# if-455-to-12khz.net
KiCad netlist of a schematic drawn in EAGLE
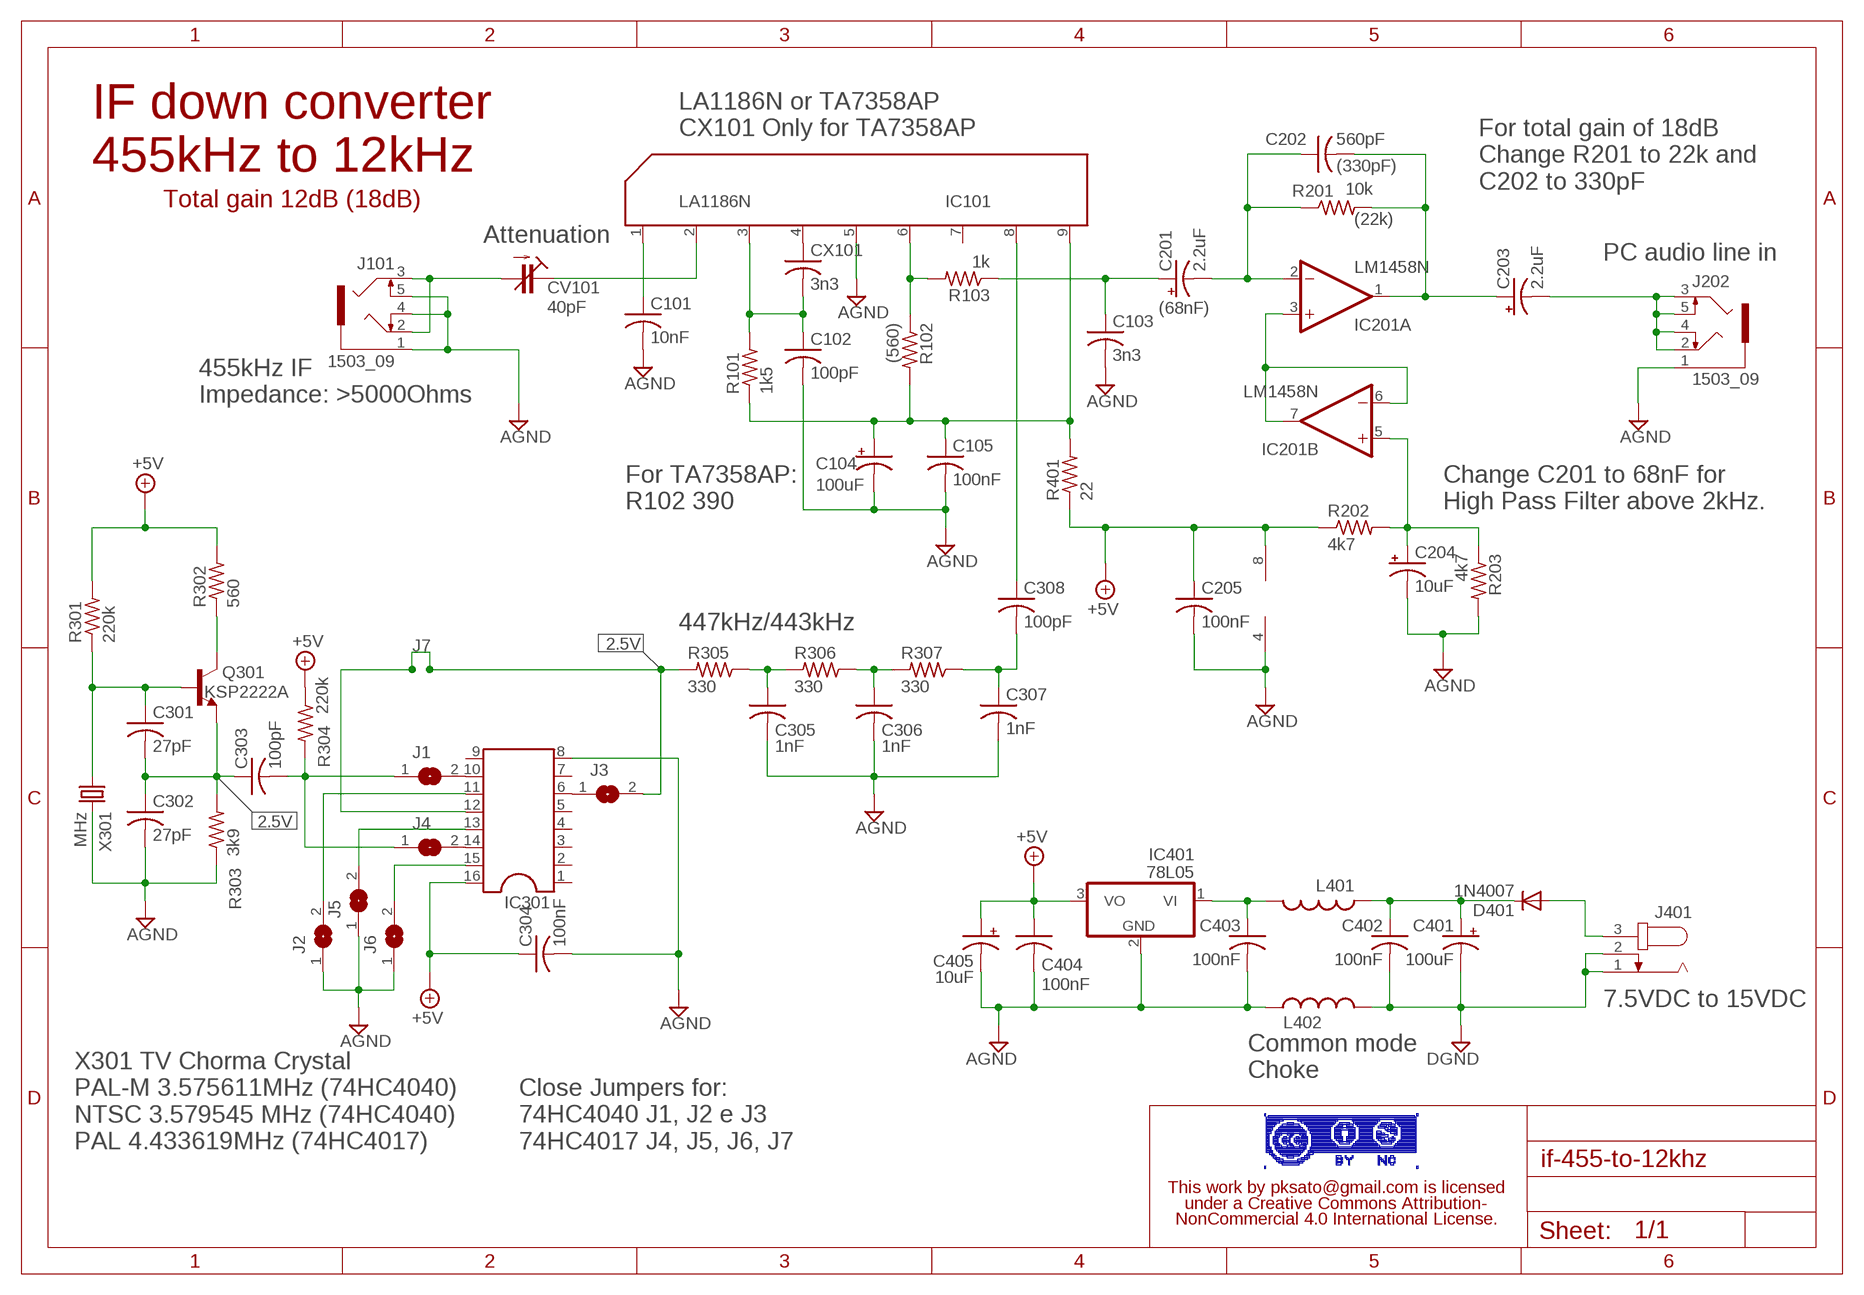
[diagram p0: schematic, sheet 1]

(export (version "E")
  (design (tool "Eeschema 10.0.6"))
  (components
    (comp (ref "C101")
      (value "10nF")
      (footprint "eagle-import:C050-025X075")
      (libsource (lib "eagle-import") (part "C-US050-025X075"))
    )
    (comp (ref "C102")
      (value "100pF")
      (footprint "eagle-import:C050-025X075")
      (libsource (lib "eagle-import") (part "C-US050-025X075"))
    )
    (comp (ref "C103")
      (value "3n3")
      (footprint "eagle-import:C050-025X075")
      (libsource (lib "eagle-import") (part "C-US050-025X075"))
    )
    (comp (ref "C104")
      (value "100uF")
      (footprint "eagle-import:E2,5-5")
      (libsource (lib "eagle-import") (part "CPOL-USE2.5-5"))
    )
    (comp (ref "C105")
      (value "100nF")
      (footprint "eagle-import:C050-025X075")
      (libsource (lib "eagle-import") (part "C-US050-025X075"))
    )
    (comp (ref "C201")
      (value "2.2uF")
      (footprint "eagle-import:E5-5")
      (libsource (lib "eagle-import") (part "CPOL-USE5-5"))
    )
    (comp (ref "C202")
      (value "560pF")
      (footprint "eagle-import:C050-025X075")
      (libsource (lib "eagle-import") (part "C-US050-025X075"))
    )
    (comp (ref "C203")
      (value "2.2uF")
      (footprint "eagle-import:E2,5-5")
      (libsource (lib "eagle-import") (part "CPOL-USE2.5-5"))
    )
    (comp (ref "C204")
      (value "10uF")
      (footprint "eagle-import:E2,5-5")
      (libsource (lib "eagle-import") (part "CPOL-USE2.5-5"))
    )
    (comp (ref "C205")
      (value "100nF")
      (footprint "eagle-import:C050-025X075")
      (libsource (lib "eagle-import") (part "C-US050-025X075"))
    )
    (comp (ref "C301")
      (value "27pF")
      (footprint "eagle-import:C050-025X075")
      (libsource (lib "eagle-import") (part "C-US050-025X075"))
    )
    (comp (ref "C302")
      (value "27pF")
      (footprint "eagle-import:C050-025X075")
      (libsource (lib "eagle-import") (part "C-US050-025X075"))
    )
    (comp (ref "C303")
      (value "100pF")
      (footprint "eagle-import:C050-025X075")
      (libsource (lib "eagle-import") (part "C-US050-025X075"))
    )
    (comp (ref "C304")
      (value "100nF")
      (footprint "eagle-import:C050-025X075")
      (libsource (lib "eagle-import") (part "C-US050-025X075"))
    )
    (comp (ref "C305")
      (value "1nF")
      (footprint "eagle-import:C050-025X075")
      (libsource (lib "eagle-import") (part "C-US050-025X075"))
    )
    (comp (ref "C306")
      (value "1nF")
      (footprint "eagle-import:C050-025X075")
      (libsource (lib "eagle-import") (part "C-US050-025X075"))
    )
    (comp (ref "C307")
      (value "1nF")
      (footprint "eagle-import:C050-025X075")
      (libsource (lib "eagle-import") (part "C-US050-025X075"))
    )
    (comp (ref "C308")
      (value "100pF")
      (footprint "eagle-import:C050-025X075")
      (libsource (lib "eagle-import") (part "C-US050-025X075"))
    )
    (comp (ref "C401")
      (value "100uF")
      (footprint "eagle-import:E2,5-5")
      (libsource (lib "eagle-import") (part "CPOL-USE2.5-5"))
    )
    (comp (ref "C402")
      (value "100nF")
      (footprint "eagle-import:C050-025X075")
      (libsource (lib "eagle-import") (part "C-US050-025X075"))
    )
    (comp (ref "C403")
      (value "100nF")
      (footprint "eagle-import:C050-025X075")
      (libsource (lib "eagle-import") (part "C-US050-025X075"))
    )
    (comp (ref "C404")
      (value "100nF")
      (footprint "eagle-import:C050-025X075")
      (libsource (lib "eagle-import") (part "C-US050-025X075"))
    )
    (comp (ref "C405")
      (value "10uF")
      (footprint "eagle-import:E2,5-5")
      (libsource (lib "eagle-import") (part "CPOL-USE2.5-5"))
    )
    (comp (ref "CV101")
      (value "40pF")
      (footprint "eagle-import:CTRIMTZ03")
      (libsource (lib "eagle-import") (part "C-TRIMMTZ03"))
    )
    (comp (ref "CX101")
      (value "3n3")
      (footprint "eagle-import:C025-025X050")
      (libsource (lib "eagle-import") (part "C-US025-025X050"))
    )
    (comp (ref "D401")
      (value "1N4007")
      (footprint "eagle-import:DO41-10")
      (libsource (lib "eagle-import") (part "1N4004"))
    )
    (comp (ref "IC101")
      (value "LA1186N")
      (footprint "eagle-import:SIP09")
      (libsource (lib "eagle-import") (part "SIP09"))
    )
    (comp (ref "IC201")
      (value "LM1458N")
      (footprint "eagle-import:DIL08")
      (libsource (lib "eagle-import") (part "1458NLM"))
    )
    (comp (ref "IC301")
      (value "DIL16")
      (footprint "eagle-import:DIL16")
      (libsource (lib "eagle-import") (part "DIL16"))
    )
    (comp (ref "IC401")
      (value "78L05")
      (footprint "eagle-import:TO92-")
      (libsource (lib "eagle-import") (part "78L-L05"))
    )
    (comp (ref "J1") (value "SJ") (footprint "eagle-import:SJ") (libsource (lib "eagle-import") (part "SJ")))
    (comp (ref "J2") (value "SJ") (footprint "eagle-import:SJ") (libsource (lib "eagle-import") (part "SJ")))
    (comp (ref "J3") (value "SJ") (footprint "eagle-import:SJ") (libsource (lib "eagle-import") (part "SJ")))
    (comp (ref "J4") (value "SJ") (footprint "eagle-import:SJ") (libsource (lib "eagle-import") (part "SJ")))
    (comp (ref "J5") (value "SJ") (footprint "eagle-import:SJ") (libsource (lib "eagle-import") (part "SJ")))
    (comp (ref "J6") (value "SJ") (footprint "eagle-import:SJ") (libsource (lib "eagle-import") (part "SJ")))
    (comp (ref "J101")
      (value "1503_09")
      (footprint "eagle-import:1503_09")
      (libsource (lib "eagle-import") (part "1503_09"))
    )
    (comp (ref "J202")
      (value "1503_09")
      (footprint "eagle-import:1503_09")
      (libsource (lib "eagle-import") (part "1503_09"))
    )
    (comp (ref "J401")
      (value "JACK-PLUG0")
      (footprint "eagle-import:SPC4077")
      (libsource (lib "eagle-import") (part "JACK-PLUG0"))
    )
    (comp (ref "L401")
      (value "L-US0207/10")
      (footprint "eagle-import:0207_10")
      (libsource (lib "eagle-import") (part "L-US0207/10"))
    )
    (comp (ref "L402")
      (value "L-US0207/10")
      (footprint "eagle-import:0207_10")
      (libsource (lib "eagle-import") (part "L-US0207/10"))
    )
    (comp (ref "Q301")
      (value "KSP2222A")
      (footprint "eagle-import:TO92-EBC")
      (libsource (lib "eagle-import") (part "-NPN-TO92-EBC2N2222"))
    )
    (comp (ref "R101")
      (value "1k5")
      (footprint "eagle-import:0207_10")
      (libsource (lib "eagle-import") (part "R-US_0207/10"))
    )
    (comp (ref "R102")
      (value "(560)")
      (footprint "eagle-import:0207_10")
      (libsource (lib "eagle-import") (part "R-US_0207/10"))
    )
    (comp (ref "R103")
      (value "1k")
      (footprint "eagle-import:0207_10")
      (libsource (lib "eagle-import") (part "R-US_0207/10"))
    )
    (comp (ref "R201")
      (value "10k")
      (footprint "eagle-import:0207_10")
      (libsource (lib "eagle-import") (part "R-US_0207/10"))
    )
    (comp (ref "R202")
      (value "4k7")
      (footprint "eagle-import:0207_10")
      (libsource (lib "eagle-import") (part "R-US_0207/10"))
    )
    (comp (ref "R203")
      (value "4k7")
      (footprint "eagle-import:0207_10")
      (libsource (lib "eagle-import") (part "R-US_0207/10"))
    )
    (comp (ref "R301")
      (value "220k")
      (footprint "eagle-import:0207_10")
      (libsource (lib "eagle-import") (part "R-US_0207/10"))
    )
    (comp (ref "R302")
      (value "560")
      (footprint "eagle-import:0207_10")
      (libsource (lib "eagle-import") (part "R-US_0207/10"))
    )
    (comp (ref "R303")
      (value "3k9")
      (footprint "eagle-import:0207_10")
      (libsource (lib "eagle-import") (part "R-US_0207/10"))
    )
    (comp (ref "R304")
      (value "220k")
      (footprint "eagle-import:0207_10")
      (libsource (lib "eagle-import") (part "R-US_0207/10"))
    )
    (comp (ref "R305")
      (value "330")
      (footprint "eagle-import:0207_10")
      (libsource (lib "eagle-import") (part "R-US_0207/10"))
    )
    (comp (ref "R306")
      (value "330")
      (footprint "eagle-import:0207_10")
      (libsource (lib "eagle-import") (part "R-US_0207/10"))
    )
    (comp (ref "R307")
      (value "330")
      (footprint "eagle-import:0207_10")
      (libsource (lib "eagle-import") (part "R-US_0207/10"))
    )
    (comp (ref "R401")
      (value "22")
      (footprint "eagle-import:0207_10")
      (libsource (lib "eagle-import") (part "R-US_0207/10"))
    )
    (comp (ref "X301")
      (value "MHz")
      (footprint "eagle-import:HC49U-LM")
      (libsource (lib "eagle-import") (part "CRYSTALHC49U-LM"))
    )
  )
  (nets
    (net (code "1") (name "+5V") (class "Default")
      (node (ref "C205") (pin "1") (pinfunction "1_1") (pintype "passive"))
      (node (ref "C304") (pin "1") (pinfunction "1_1") (pintype "passive"))
      (node (ref "C404") (pin "1") (pinfunction "1_1") (pintype "passive"))
      (node (ref "C405") (pin "+") (pinfunction "+_+") (pintype "passive"))
      (node (ref "IC201") (pin "8") (pinfunction "V+_8") (pintype "power_in"))
      (node (ref "IC301") (pin "16") (pinfunction "16_16") (pintype "passive"))
      (node (ref "IC401") (pin "3") (pinfunction "VO_3") (pintype "passive"))
      (node (ref "R202") (pin "1") (pinfunction "1_1") (pintype "passive"))
      (node (ref "R301") (pin "2") (pinfunction "2_2") (pintype "passive"))
      (node (ref "R302") (pin "2") (pinfunction "2_2") (pintype "passive"))
      (node (ref "R304") (pin "1") (pinfunction "1_1") (pintype "passive"))
      (node (ref "R401") (pin "1") (pinfunction "1_1") (pintype "passive"))
    )
    (net (code "2") (name "AGND") (class "Default")
      (node (ref "C101") (pin "2") (pinfunction "2_2") (pintype "passive"))
      (node (ref "C102") (pin "2") (pinfunction "2_2") (pintype "passive"))
      (node (ref "C103") (pin "2") (pinfunction "2_2") (pintype "passive"))
      (node (ref "C104") (pin "-") (pinfunction "-_-") (pintype "passive"))
      (node (ref "C105") (pin "2") (pinfunction "2_2") (pintype "passive"))
      (node (ref "C204") (pin "-") (pinfunction "-_-") (pintype "passive"))
      (node (ref "C205") (pin "2") (pinfunction "2_2") (pintype "passive"))
      (node (ref "C302") (pin "2") (pinfunction "2_2") (pintype "passive"))
      (node (ref "C304") (pin "2") (pinfunction "2_2") (pintype "passive"))
      (node (ref "C305") (pin "2") (pinfunction "2_2") (pintype "passive"))
      (node (ref "C306") (pin "2") (pinfunction "2_2") (pintype "passive"))
      (node (ref "C307") (pin "2") (pinfunction "2_2") (pintype "passive"))
      (node (ref "C403") (pin "2") (pinfunction "2_2") (pintype "passive"))
      (node (ref "C404") (pin "2") (pinfunction "2_2") (pintype "passive"))
      (node (ref "C405") (pin "-") (pinfunction "-_-") (pintype "passive"))
      (node (ref "IC101") (pin "5") (pinfunction "5_5") (pintype "passive"))
      (node (ref "IC201") (pin "4") (pinfunction "V-_4") (pintype "power_in"))
      (node (ref "IC301") (pin "8") (pinfunction "8_8") (pintype "passive"))
      (node (ref "IC401") (pin "2") (pinfunction "GND_2") (pintype "passive"))
      (node (ref "J101") (pin "1") (pinfunction "1_1") (pintype "passive"))
      (node (ref "J101") (pin "4") (pinfunction "4_4") (pintype "passive"))
      (node (ref "J101") (pin "5") (pinfunction "5_5") (pintype "passive"))
      (node (ref "J2") (pin "1") (pinfunction "1_1") (pintype "passive"))
      (node (ref "J202") (pin "1") (pinfunction "1_1") (pintype "passive"))
      (node (ref "J5") (pin "1") (pinfunction "1_1") (pintype "passive"))
      (node (ref "J6") (pin "1") (pinfunction "1_1") (pintype "passive"))
      (node (ref "L402") (pin "2") (pinfunction "2_2") (pintype "passive"))
      (node (ref "R203") (pin "2") (pinfunction "2_2") (pintype "passive"))
      (node (ref "R303") (pin "1") (pinfunction "1_1") (pintype "passive"))
      (node (ref "X301") (pin "2") (pinfunction "2_2") (pintype "passive"))
    )
    (net (code "3") (name "DGND") (class "Default")
      (node (ref "C401") (pin "-") (pinfunction "-_-") (pintype "passive"))
      (node (ref "C402") (pin "2") (pinfunction "2_2") (pintype "passive"))
      (node (ref "J401") (pin "1") (pinfunction "1_1") (pintype "passive"))
      (node (ref "J401") (pin "2") (pinfunction "2_2") (pintype "passive"))
      (node (ref "L402") (pin "1") (pinfunction "1_1") (pintype "passive"))
    )
    (net (code "4") (name "Net-(C101-Pad1)") (class "Default")
      (node (ref "C101") (pin "1") (pinfunction "1_1") (pintype "passive"))
      (node (ref "IC101") (pin "1") (pinfunction "1_1") (pintype "passive"))
    )
    (net (code "5") (name "Net-(C102-Pad1)") (class "Default")
      (node (ref "C102") (pin "1") (pinfunction "1_1") (pintype "passive"))
      (node (ref "CX101") (pin "2") (pinfunction "2_2") (pintype "passive"))
      (node (ref "IC101") (pin "3") (pinfunction "3_3") (pintype "passive"))
      (node (ref "R101") (pin "2") (pinfunction "2_2") (pintype "passive"))
    )
    (net (code "6") (name "Net-(C103-Pad1)") (class "Default")
      (node (ref "C103") (pin "1") (pinfunction "1_1") (pintype "passive"))
      (node (ref "C201") (pin "+") (pinfunction "+_+") (pintype "passive"))
      (node (ref "R103") (pin "1") (pinfunction "1_1") (pintype "passive"))
    )
    (net (code "7") (name "Net-(C104-Pad+)") (class "Default")
      (node (ref "C104") (pin "+") (pinfunction "+_+") (pintype "passive"))
      (node (ref "C105") (pin "1") (pinfunction "1_1") (pintype "passive"))
      (node (ref "IC101") (pin "9") (pinfunction "9_9") (pintype "passive"))
      (node (ref "R101") (pin "1") (pinfunction "1_1") (pintype "passive"))
      (node (ref "R102") (pin "2") (pinfunction "2_2") (pintype "passive"))
      (node (ref "R401") (pin "2") (pinfunction "2_2") (pintype "passive"))
    )
    (net (code "8") (name "Net-(C203-Pad-)") (class "Default")
      (node (ref "C203") (pin "-") (pinfunction "-_-") (pintype "passive"))
      (node (ref "J202") (pin "2") (pinfunction "2_2") (pintype "passive"))
      (node (ref "J202") (pin "3") (pinfunction "3_3") (pintype "passive"))
      (node (ref "J202") (pin "4") (pinfunction "4_4") (pintype "passive"))
      (node (ref "J202") (pin "5") (pinfunction "5_5") (pintype "passive"))
    )
    (net (code "9") (name "Net-(C301-Pad1)") (class "Default")
      (node (ref "C301") (pin "1") (pinfunction "1_1") (pintype "passive"))
      (node (ref "Q301") (pin "B") (pinfunction "B_B") (pintype "passive"))
      (node (ref "R301") (pin "1") (pinfunction "1_1") (pintype "passive"))
      (node (ref "X301") (pin "1") (pinfunction "1_1") (pintype "passive"))
    )
    (net (code "10") (name "Net-(C301-Pad2)") (class "Default")
      (node (ref "C301") (pin "2") (pinfunction "2_2") (pintype "passive"))
      (node (ref "C302") (pin "1") (pinfunction "1_1") (pintype "passive"))
      (node (ref "C303") (pin "1") (pinfunction "1_1") (pintype "passive"))
      (node (ref "Q301") (pin "E") (pinfunction "E_E") (pintype "passive"))
      (node (ref "R303") (pin "2") (pinfunction "2_2") (pintype "passive"))
    )
    (net (code "11") (name "Net-(C303-Pad2)") (class "Default")
      (node (ref "C303") (pin "2") (pinfunction "2_2") (pintype "passive"))
      (node (ref "J1") (pin "1") (pinfunction "1_1") (pintype "passive"))
      (node (ref "J4") (pin "1") (pinfunction "1_1") (pintype "passive"))
      (node (ref "R304") (pin "2") (pinfunction "2_2") (pintype "passive"))
    )
    (net (code "12") (name "Net-(C305-Pad1)") (class "Default")
      (node (ref "C305") (pin "1") (pinfunction "1_1") (pintype "passive"))
      (node (ref "R305") (pin "1") (pinfunction "1_1") (pintype "passive"))
      (node (ref "R306") (pin "2") (pinfunction "2_2") (pintype "passive"))
    )
    (net (code "13") (name "Net-(C306-Pad1)") (class "Default")
      (node (ref "C306") (pin "1") (pinfunction "1_1") (pintype "passive"))
      (node (ref "R306") (pin "1") (pinfunction "1_1") (pintype "passive"))
      (node (ref "R307") (pin "2") (pinfunction "2_2") (pintype "passive"))
    )
    (net (code "14") (name "Net-(C307-Pad1)") (class "Default")
      (node (ref "C307") (pin "1") (pinfunction "1_1") (pintype "passive"))
      (node (ref "C308") (pin "2") (pinfunction "2_2") (pintype "passive"))
      (node (ref "R307") (pin "1") (pinfunction "1_1") (pintype "passive"))
    )
    (net (code "15") (name "Net-(C308-Pad1)") (class "Default")
      (node (ref "C308") (pin "1") (pinfunction "1_1") (pintype "passive"))
      (node (ref "IC101") (pin "8") (pinfunction "8_8") (pintype "passive"))
    )
    (net (code "16") (name "Net-(C401-Pad+)") (class "Default")
      (node (ref "C401") (pin "+") (pinfunction "+_+") (pintype "passive"))
      (node (ref "C402") (pin "1") (pinfunction "1_1") (pintype "passive"))
      (node (ref "D401") (pin "C") (pinfunction "C_C") (pintype "passive"))
      (node (ref "L401") (pin "2") (pinfunction "2_2") (pintype "passive"))
    )
    (net (code "17") (name "Net-(CV101-A)") (class "Default")
      (node (ref "CV101") (pin "2") (pinfunction "A_2") (pintype "passive"))
      (node (ref "J101") (pin "2") (pinfunction "2_2") (pintype "passive"))
      (node (ref "J101") (pin "3") (pinfunction "3_3") (pintype "passive"))
    )
    (net (code "18") (name "Net-(CV101-E)") (class "Default")
      (node (ref "CV101") (pin "1") (pinfunction "E_1") (pintype "passive"))
      (node (ref "IC101") (pin "2") (pinfunction "2_2") (pintype "passive"))
    )
    (net (code "19") (name "Net-(CX101-Pad1)") (class "Default")
      (node (ref "CX101") (pin "1") (pinfunction "1_1") (pintype "passive"))
      (node (ref "IC101") (pin "4") (pinfunction "4_4") (pintype "passive"))
    )
    (net (code "20") (name "Net-(D401-PadA)") (class "Default")
      (node (ref "D401") (pin "A") (pinfunction "A_A") (pintype "passive"))
      (node (ref "J401") (pin "3") (pinfunction "3_3") (pintype "passive"))
    )
    (net (code "21") (name "Net-(IC101-Pad6)") (class "Default")
      (node (ref "IC101") (pin "6") (pinfunction "6_6") (pintype "passive"))
      (node (ref "R102") (pin "1") (pinfunction "1_1") (pintype "passive"))
      (node (ref "R103") (pin "2") (pinfunction "2_2") (pintype "passive"))
    )
    (net (code "22") (name "Net-(IC201A-+IN)") (class "Default")
      (node (ref "IC201") (pin "3") (pinfunction "+IN_3") (pintype "input"))
      (node (ref "IC201") (pin "6") (pinfunction "-IN_6") (pintype "input"))
      (node (ref "IC201") (pin "7") (pinfunction "OUT_7") (pintype "output"))
    )
    (net (code "23") (name "Net-(IC201A--IN)") (class "Default")
      (node (ref "C201") (pin "-") (pinfunction "-_-") (pintype "passive"))
      (node (ref "C202") (pin "1") (pinfunction "1_1") (pintype "passive"))
      (node (ref "IC201") (pin "2") (pinfunction "-IN_2") (pintype "input"))
      (node (ref "R201") (pin "1") (pinfunction "1_1") (pintype "passive"))
    )
    (net (code "24") (name "Net-(IC201A-OUT)") (class "Default")
      (node (ref "C202") (pin "2") (pinfunction "2_2") (pintype "passive"))
      (node (ref "C203") (pin "+") (pinfunction "+_+") (pintype "passive"))
      (node (ref "IC201") (pin "1") (pinfunction "OUT_1") (pintype "output"))
      (node (ref "R201") (pin "2") (pinfunction "2_2") (pintype "passive"))
    )
    (net (code "25") (name "Net-(IC201B-+IN)") (class "Default")
      (node (ref "C204") (pin "+") (pinfunction "+_+") (pintype "passive"))
      (node (ref "IC201") (pin "5") (pinfunction "+IN_5") (pintype "input"))
      (node (ref "R202") (pin "2") (pinfunction "2_2") (pintype "passive"))
      (node (ref "R203") (pin "1") (pinfunction "1_1") (pintype "passive"))
    )
    (net (code "26") (name "Net-(IC301-Pad6)") (class "Default")
      (node (ref "IC301") (pin "6") (pinfunction "6_6") (pintype "passive"))
      (node (ref "J3") (pin "1") (pinfunction "1_1") (pintype "passive"))
    )
    (net (code "27") (name "Net-(IC301-Pad10)") (class "Default")
      (node (ref "IC301") (pin "10") (pinfunction "10_10") (pintype "passive"))
      (node (ref "J1") (pin "2") (pinfunction "2_2") (pintype "passive"))
    )
    (net (code "28") (name "Net-(IC301-Pad11)") (class "Default")
      (node (ref "IC301") (pin "11") (pinfunction "11_11") (pintype "passive"))
      (node (ref "J2") (pin "2") (pinfunction "2_2") (pintype "passive"))
    )
    (net (code "29") (name "Net-(IC301-Pad12)") (class "Default")
      (node (ref "IC301") (pin "12") (pinfunction "12_12") (pintype "passive"))
      (node (ref "J3") (pin "2") (pinfunction "2_2") (pintype "passive"))
      (node (ref "R305") (pin "2") (pinfunction "2_2") (pintype "passive"))
    )
    (net (code "30") (name "Net-(IC301-Pad13)") (class "Default")
      (node (ref "IC301") (pin "13") (pinfunction "13_13") (pintype "passive"))
      (node (ref "J5") (pin "2") (pinfunction "2_2") (pintype "passive"))
    )
    (net (code "31") (name "Net-(IC301-Pad14)") (class "Default")
      (node (ref "IC301") (pin "14") (pinfunction "14_14") (pintype "passive"))
      (node (ref "J4") (pin "2") (pinfunction "2_2") (pintype "passive"))
    )
    (net (code "32") (name "Net-(IC301-Pad15)") (class "Default")
      (node (ref "IC301") (pin "15") (pinfunction "15_15") (pintype "passive"))
      (node (ref "J6") (pin "2") (pinfunction "2_2") (pintype "passive"))
    )
    (net (code "33") (name "Net-(IC401-VI)") (class "Default")
      (node (ref "C403") (pin "1") (pinfunction "1_1") (pintype "passive"))
      (node (ref "IC401") (pin "1") (pinfunction "VI_1") (pintype "input"))
      (node (ref "L401") (pin "1") (pinfunction "1_1") (pintype "passive"))
    )
    (net (code "34") (name "Net-(Q301-PadC)") (class "Default")
      (node (ref "Q301") (pin "C") (pinfunction "C_C") (pintype "passive"))
      (node (ref "R302") (pin "1") (pinfunction "1_1") (pintype "passive"))
    )
    (net (code "35") (name "unconnected-(IC101-Pad7)") (class "Default")
      (node (ref "IC101") (pin "7") (pinfunction "7_7") (pintype "passive"))
    )
    (net (code "36") (name "unconnected-(IC301-Pad1)") (class "Default")
      (node (ref "IC301") (pin "1") (pinfunction "1_1") (pintype "passive"))
    )
    (net (code "37") (name "unconnected-(IC301-Pad2)") (class "Default")
      (node (ref "IC301") (pin "2") (pinfunction "2_2") (pintype "passive"))
    )
    (net (code "38") (name "unconnected-(IC301-Pad3)") (class "Default")
      (node (ref "IC301") (pin "3") (pinfunction "3_3") (pintype "passive"))
    )
    (net (code "39") (name "unconnected-(IC301-Pad4)") (class "Default")
      (node (ref "IC301") (pin "4") (pinfunction "4_4") (pintype "passive"))
    )
    (net (code "40") (name "unconnected-(IC301-Pad5)") (class "Default")
      (node (ref "IC301") (pin "5") (pinfunction "5_5") (pintype "passive"))
    )
    (net (code "41") (name "unconnected-(IC301-Pad7)") (class "Default")
      (node (ref "IC301") (pin "7") (pinfunction "7_7") (pintype "passive"))
    )
    (net (code "42") (name "unconnected-(IC301-Pad9)") (class "Default")
      (node (ref "IC301") (pin "9") (pinfunction "9_9") (pintype "passive"))
    )
  )
)
